# CharlieBreakout.net
KiCad netlist of a schematic drawn in EAGLE
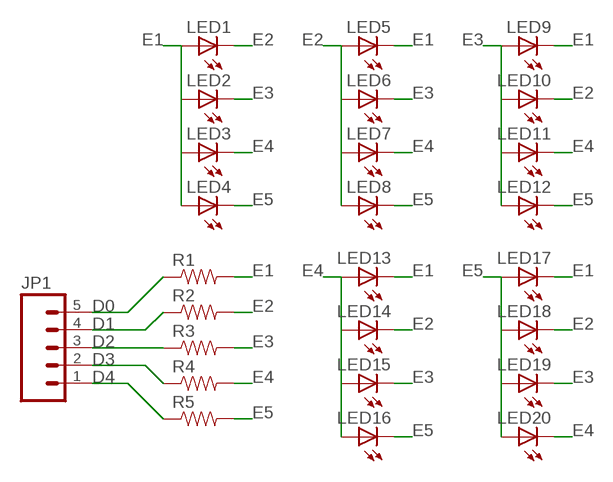
[diagram p0: schematic, sheet 1]

(export (version "E")
  (design (tool "Eeschema 10.0.6"))
  (components
    (comp (ref "JP1")
      (value "M05PTH")
      (footprint "eagle-import:1X05")
      (libsource (lib "eagle-import") (part "M05PTH"))
    )
    (comp (ref "LED1")
      (value "LED3MM")
      (footprint "eagle-import:LED3MM")
      (libsource (lib "eagle-import") (part "LED3MM"))
    )
    (comp (ref "LED2")
      (value "LED3MM")
      (footprint "eagle-import:LED3MM")
      (libsource (lib "eagle-import") (part "LED3MM"))
    )
    (comp (ref "LED3")
      (value "LED3MM")
      (footprint "eagle-import:LED3MM")
      (libsource (lib "eagle-import") (part "LED3MM"))
    )
    (comp (ref "LED4")
      (value "LED3MM")
      (footprint "eagle-import:LED3MM")
      (libsource (lib "eagle-import") (part "LED3MM"))
    )
    (comp (ref "LED5")
      (value "LED3MM")
      (footprint "eagle-import:LED3MM")
      (libsource (lib "eagle-import") (part "LED3MM"))
    )
    (comp (ref "LED6")
      (value "LED3MM")
      (footprint "eagle-import:LED3MM")
      (libsource (lib "eagle-import") (part "LED3MM"))
    )
    (comp (ref "LED7")
      (value "LED3MM")
      (footprint "eagle-import:LED3MM")
      (libsource (lib "eagle-import") (part "LED3MM"))
    )
    (comp (ref "LED8")
      (value "LED3MM")
      (footprint "eagle-import:LED3MM")
      (libsource (lib "eagle-import") (part "LED3MM"))
    )
    (comp (ref "LED9")
      (value "LED3MM")
      (footprint "eagle-import:LED3MM")
      (libsource (lib "eagle-import") (part "LED3MM"))
    )
    (comp (ref "LED10")
      (value "LED3MM")
      (footprint "eagle-import:LED3MM")
      (libsource (lib "eagle-import") (part "LED3MM"))
    )
    (comp (ref "LED11")
      (value "LED3MM")
      (footprint "eagle-import:LED3MM")
      (libsource (lib "eagle-import") (part "LED3MM"))
    )
    (comp (ref "LED12")
      (value "LED3MM")
      (footprint "eagle-import:LED3MM")
      (libsource (lib "eagle-import") (part "LED3MM"))
    )
    (comp (ref "LED13")
      (value "LED3MM")
      (footprint "eagle-import:LED3MM")
      (libsource (lib "eagle-import") (part "LED3MM"))
    )
    (comp (ref "LED14")
      (value "LED3MM")
      (footprint "eagle-import:LED3MM")
      (libsource (lib "eagle-import") (part "LED3MM"))
    )
    (comp (ref "LED15")
      (value "LED3MM")
      (footprint "eagle-import:LED3MM")
      (libsource (lib "eagle-import") (part "LED3MM"))
    )
    (comp (ref "LED16")
      (value "LED3MM")
      (footprint "eagle-import:LED3MM")
      (libsource (lib "eagle-import") (part "LED3MM"))
    )
    (comp (ref "LED17")
      (value "LED3MM")
      (footprint "eagle-import:LED3MM")
      (libsource (lib "eagle-import") (part "LED3MM"))
    )
    (comp (ref "LED18")
      (value "LED3MM")
      (footprint "eagle-import:LED3MM")
      (libsource (lib "eagle-import") (part "LED3MM"))
    )
    (comp (ref "LED19")
      (value "LED3MM")
      (footprint "eagle-import:LED3MM")
      (libsource (lib "eagle-import") (part "LED3MM"))
    )
    (comp (ref "LED20")
      (value "LED3MM")
      (footprint "eagle-import:LED3MM")
      (libsource (lib "eagle-import") (part "LED3MM"))
    )
    (comp (ref "R1")
      (value "RESISTORAXIAL-0.3")
      (footprint "eagle-import:AXIAL-0.3")
      (libsource (lib "eagle-import") (part "RESISTORAXIAL-0.3"))
    )
    (comp (ref "R2")
      (value "RESISTORAXIAL-0.3")
      (footprint "eagle-import:AXIAL-0.3")
      (libsource (lib "eagle-import") (part "RESISTORAXIAL-0.3"))
    )
    (comp (ref "R3")
      (value "RESISTORAXIAL-0.3")
      (footprint "eagle-import:AXIAL-0.3")
      (libsource (lib "eagle-import") (part "RESISTORAXIAL-0.3"))
    )
    (comp (ref "R4")
      (value "RESISTORAXIAL-0.3")
      (footprint "eagle-import:AXIAL-0.3")
      (libsource (lib "eagle-import") (part "RESISTORAXIAL-0.3"))
    )
    (comp (ref "R5")
      (value "RESISTORAXIAL-0.3")
      (footprint "eagle-import:AXIAL-0.3")
      (libsource (lib "eagle-import") (part "RESISTORAXIAL-0.3"))
    )
  )
  (nets
    (net (code "1") (name "/D0") (class "Default")
      (node (ref "JP1") (pin "5") (pinfunction "5_5") (pintype "passive"))
      (node (ref "R1") (pin "P$1") (pinfunction "1_P$1") (pintype "passive"))
    )
    (net (code "2") (name "/D1") (class "Default")
      (node (ref "JP1") (pin "4") (pinfunction "4_4") (pintype "passive"))
      (node (ref "R2") (pin "P$1") (pinfunction "1_P$1") (pintype "passive"))
    )
    (net (code "3") (name "/D2") (class "Default")
      (node (ref "JP1") (pin "3") (pinfunction "3_3") (pintype "passive"))
      (node (ref "R3") (pin "P$1") (pinfunction "1_P$1") (pintype "passive"))
    )
    (net (code "4") (name "/D3") (class "Default")
      (node (ref "JP1") (pin "2") (pinfunction "2_2") (pintype "passive"))
      (node (ref "R4") (pin "P$1") (pinfunction "1_P$1") (pintype "passive"))
    )
    (net (code "5") (name "/D4") (class "Default")
      (node (ref "JP1") (pin "1") (pinfunction "1_1") (pintype "passive"))
      (node (ref "R5") (pin "P$1") (pinfunction "1_P$1") (pintype "passive"))
    )
    (net (code "6") (name "/E1") (class "Default")
      (node (ref "LED1") (pin "A") (pinfunction "A_A") (pintype "passive"))
      (node (ref "LED13") (pin "K") (pinfunction "C_K") (pintype "passive"))
      (node (ref "LED17") (pin "K") (pinfunction "C_K") (pintype "passive"))
      (node (ref "LED2") (pin "A") (pinfunction "A_A") (pintype "passive"))
      (node (ref "LED3") (pin "A") (pinfunction "A_A") (pintype "passive"))
      (node (ref "LED4") (pin "A") (pinfunction "A_A") (pintype "passive"))
      (node (ref "LED5") (pin "K") (pinfunction "C_K") (pintype "passive"))
      (node (ref "LED9") (pin "K") (pinfunction "C_K") (pintype "passive"))
      (node (ref "R1") (pin "P$2") (pinfunction "2_P$2") (pintype "passive"))
    )
    (net (code "7") (name "/E2") (class "Default")
      (node (ref "LED1") (pin "K") (pinfunction "C_K") (pintype "passive"))
      (node (ref "LED10") (pin "K") (pinfunction "C_K") (pintype "passive"))
      (node (ref "LED14") (pin "K") (pinfunction "C_K") (pintype "passive"))
      (node (ref "LED18") (pin "K") (pinfunction "C_K") (pintype "passive"))
      (node (ref "LED5") (pin "A") (pinfunction "A_A") (pintype "passive"))
      (node (ref "LED6") (pin "A") (pinfunction "A_A") (pintype "passive"))
      (node (ref "LED7") (pin "A") (pinfunction "A_A") (pintype "passive"))
      (node (ref "LED8") (pin "A") (pinfunction "A_A") (pintype "passive"))
      (node (ref "R2") (pin "P$2") (pinfunction "2_P$2") (pintype "passive"))
    )
    (net (code "8") (name "/E3") (class "Default")
      (node (ref "LED10") (pin "A") (pinfunction "A_A") (pintype "passive"))
      (node (ref "LED11") (pin "A") (pinfunction "A_A") (pintype "passive"))
      (node (ref "LED12") (pin "A") (pinfunction "A_A") (pintype "passive"))
      (node (ref "LED15") (pin "K") (pinfunction "C_K") (pintype "passive"))
      (node (ref "LED19") (pin "K") (pinfunction "C_K") (pintype "passive"))
      (node (ref "LED2") (pin "K") (pinfunction "C_K") (pintype "passive"))
      (node (ref "LED6") (pin "K") (pinfunction "C_K") (pintype "passive"))
      (node (ref "LED9") (pin "A") (pinfunction "A_A") (pintype "passive"))
      (node (ref "R3") (pin "P$2") (pinfunction "2_P$2") (pintype "passive"))
    )
    (net (code "9") (name "/E4") (class "Default")
      (node (ref "LED11") (pin "K") (pinfunction "C_K") (pintype "passive"))
      (node (ref "LED13") (pin "A") (pinfunction "A_A") (pintype "passive"))
      (node (ref "LED14") (pin "A") (pinfunction "A_A") (pintype "passive"))
      (node (ref "LED15") (pin "A") (pinfunction "A_A") (pintype "passive"))
      (node (ref "LED16") (pin "A") (pinfunction "A_A") (pintype "passive"))
      (node (ref "LED20") (pin "K") (pinfunction "C_K") (pintype "passive"))
      (node (ref "LED3") (pin "K") (pinfunction "C_K") (pintype "passive"))
      (node (ref "LED7") (pin "K") (pinfunction "C_K") (pintype "passive"))
      (node (ref "R4") (pin "P$2") (pinfunction "2_P$2") (pintype "passive"))
    )
    (net (code "10") (name "/E5") (class "Default")
      (node (ref "LED12") (pin "K") (pinfunction "C_K") (pintype "passive"))
      (node (ref "LED16") (pin "K") (pinfunction "C_K") (pintype "passive"))
      (node (ref "LED17") (pin "A") (pinfunction "A_A") (pintype "passive"))
      (node (ref "LED18") (pin "A") (pinfunction "A_A") (pintype "passive"))
      (node (ref "LED19") (pin "A") (pinfunction "A_A") (pintype "passive"))
      (node (ref "LED20") (pin "A") (pinfunction "A_A") (pintype "passive"))
      (node (ref "LED4") (pin "K") (pinfunction "C_K") (pintype "passive"))
      (node (ref "LED8") (pin "K") (pinfunction "C_K") (pintype "passive"))
      (node (ref "R5") (pin "P$2") (pinfunction "2_P$2") (pintype "passive"))
    )
  )
)
